# shinobi_solar.net
KiCad netlist of a schematic drawn in EAGLE
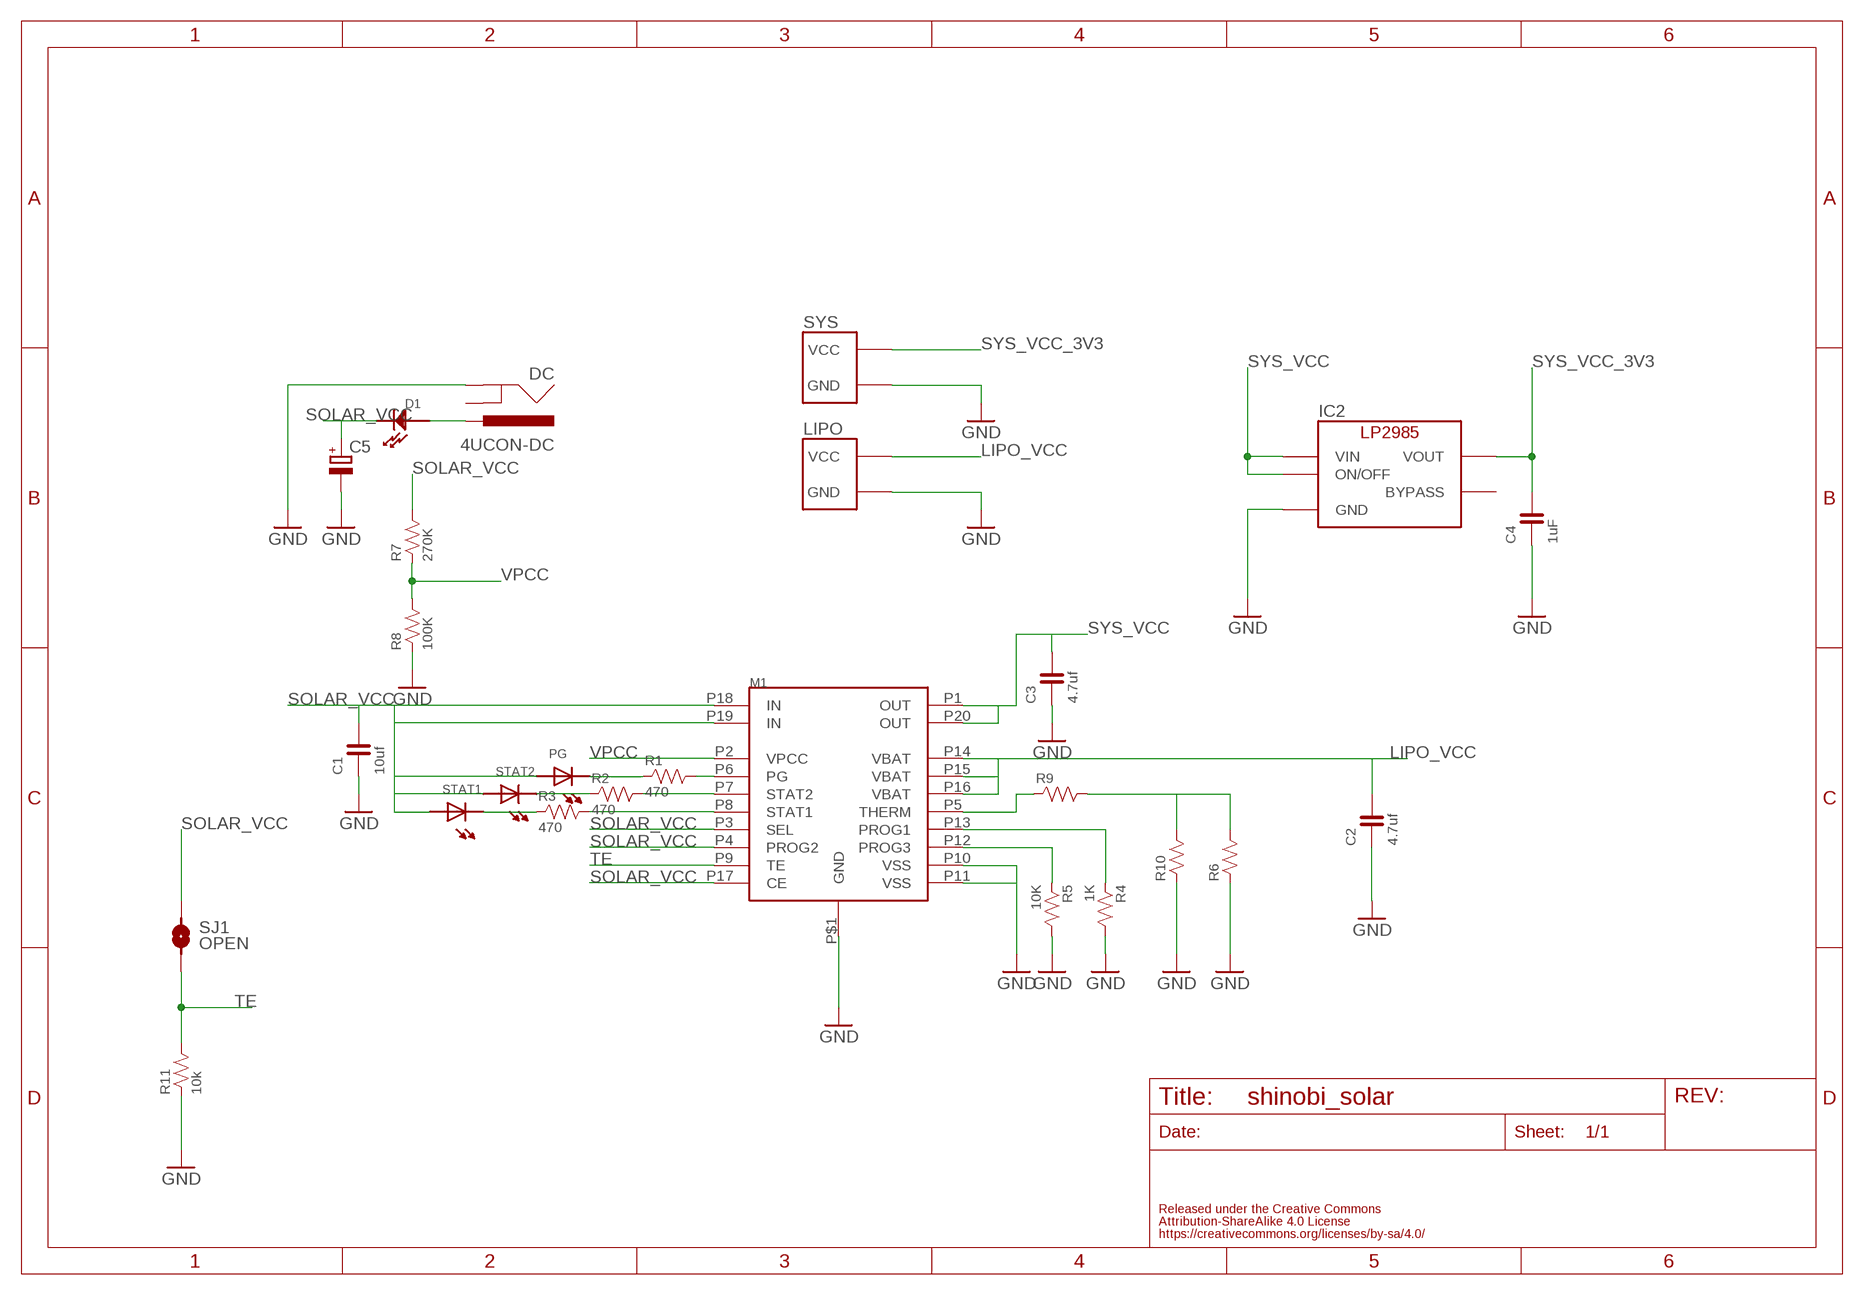
[diagram p0: schematic, sheet 1]

(export (version "E")
  (design (tool "Eeschema 10.0.6"))
  (components
    (comp (ref "C1")
      (value "10uf")
      (footprint "eagle-import:0603")
      (libsource (lib "eagle-import") (part "CAPACITOR-0603"))
    )
    (comp (ref "C2")
      (value "4.7uf")
      (footprint "eagle-import:0603")
      (libsource (lib "eagle-import") (part "CAPACITOR-0603"))
    )
    (comp (ref "C3")
      (value "4.7uf")
      (footprint "eagle-import:0603")
      (libsource (lib "eagle-import") (part "CAPACITOR-0603"))
    )
    (comp (ref "C4")
      (value "1uF")
      (footprint "eagle-import:0603")
      (libsource (lib "eagle-import") (part "CAPACITOR-0603"))
    )
    (comp (ref "C5")
      (value "CPOL-EUE5-13")
      (footprint "eagle-import:E5-13")
      (libsource (lib "eagle-import") (part "CPOL-EUE5-13"))
    )
    (comp (ref "D1")
      (value "DIODEDO-214AC")
      (footprint "eagle-import:DO-214AC")
      (libsource (lib "eagle-import") (part "DIODEDO-214AC"))
    )
    (comp (ref "DC")
      (value "4UCON-DC")
      (footprint "eagle-import:4UCON-DC")
      (libsource (lib "eagle-import") (part "4UCON-DC"))
    )
    (comp (ref "IC2")
      (value "LP2985-33DBV")
      (footprint "eagle-import:SOT-23-5")
      (libsource (lib "eagle-import") (part "LP2985-33DBV"))
    )
    (comp (ref "LIPO")
      (value "FABO_BRICK_2PIN_SIDE")
      (footprint "eagle-import:FABO_BRICK_2PIN_S02B−PASK-2_SILK")
      (libsource (lib "eagle-import") (part "FABO_BRICK_2PIN_SIDE"))
    )
    (comp (ref "M1")
      (value "MCP73871")
      (footprint "eagle-import:QFN")
      (libsource (lib "eagle-import") (part "MCP73871"))
    )
    (comp (ref "PG")
      (value "LED-0603")
      (footprint "eagle-import:0603")
      (libsource (lib "eagle-import") (part "LED-0603"))
    )
    (comp (ref "R1")
      (value "470")
      (footprint "eagle-import:0603")
      (libsource (lib "eagle-import") (part "RESISTOR-0603"))
    )
    (comp (ref "R2")
      (value "470")
      (footprint "eagle-import:0603")
      (libsource (lib "eagle-import") (part "RESISTOR-0603"))
    )
    (comp (ref "R3")
      (value "470")
      (footprint "eagle-import:0603")
      (libsource (lib "eagle-import") (part "RESISTOR-0603"))
    )
    (comp (ref "R4")
      (value "1K")
      (footprint "eagle-import:0603")
      (libsource (lib "eagle-import") (part "RESISTOR-0603"))
    )
    (comp (ref "R5")
      (value "10K")
      (footprint "eagle-import:0603")
      (libsource (lib "eagle-import") (part "RESISTOR-0603"))
    )
    (comp (ref "R6")
      (value "RESISTOR-0603")
      (footprint "eagle-import:0603")
      (libsource (lib "eagle-import") (part "RESISTOR-0603"))
    )
    (comp (ref "R7")
      (value "270K")
      (footprint "eagle-import:0603")
      (libsource (lib "eagle-import") (part "RESISTOR-0603"))
    )
    (comp (ref "R8")
      (value "100K")
      (footprint "eagle-import:0603")
      (libsource (lib "eagle-import") (part "RESISTOR-0603"))
    )
    (comp (ref "R9")
      (value "RESISTOR-0603")
      (footprint "eagle-import:0603")
      (libsource (lib "eagle-import") (part "RESISTOR-0603"))
    )
    (comp (ref "R10")
      (value "RESISTOR-AXL-REGULAR")
      (footprint "eagle-import:AXL-REGULAR")
      (libsource (lib "eagle-import") (part "RESISTOR-AXL-REGULAR"))
    )
    (comp (ref "R11")
      (value "10k")
      (footprint "eagle-import:0603")
      (libsource (lib "eagle-import") (part "RESISTOR-0603"))
    )
    (comp (ref "SJ1")
      (value "OPEN")
      (footprint "eagle-import:SMD-JUMPER-2")
      (libsource (lib "eagle-import") (part "SMD-JUMPER-2"))
    )
    (comp (ref "STAT1")
      (value "LED-0603")
      (footprint "eagle-import:0603")
      (libsource (lib "eagle-import") (part "LED-0603"))
    )
    (comp (ref "STAT2")
      (value "LED-0603")
      (footprint "eagle-import:0603")
      (libsource (lib "eagle-import") (part "LED-0603"))
    )
    (comp (ref "SYS")
      (value "FABO_BRICK_2PIN_SIDE")
      (footprint "eagle-import:FABO_BRICK_2PIN_S02B−PASK-2_SILK")
      (libsource (lib "eagle-import") (part "FABO_BRICK_2PIN_SIDE"))
    )
  )
  (nets
    (net (code "1") (name "/LIPO_VCC") (class "Default")
      (node (ref "C2") (pin "2") (pinfunction "2_2") (pintype "passive"))
      (node (ref "LIPO") (pin "VCC") (pinfunction "VCC_VCC") (pintype "bidirectional"))
      (node (ref "M1") (pin "P14") (pinfunction "VBAT_P14") (pintype "bidirectional"))
      (node (ref "M1") (pin "P15") (pinfunction "VBAT_P15") (pintype "bidirectional"))
      (node (ref "M1") (pin "P16") (pinfunction "VBAT_P16") (pintype "bidirectional"))
    )
    (net (code "2") (name "/SOLAR_VCC") (class "Default")
      (node (ref "C1") (pin "2") (pinfunction "2_2") (pintype "passive"))
      (node (ref "C5") (pin "+") (pinfunction "+_+") (pintype "passive"))
      (node (ref "D1") (pin "ANODE") (pinfunction "ANODE_ANODE") (pintype "bidirectional"))
      (node (ref "M1") (pin "P17") (pinfunction "CE_P17") (pintype "bidirectional"))
      (node (ref "M1") (pin "P18") (pinfunction "IN_P18") (pintype "bidirectional"))
      (node (ref "M1") (pin "P19") (pinfunction "IN_P19") (pintype "bidirectional"))
      (node (ref "M1") (pin "P3") (pinfunction "SEL_P3") (pintype "bidirectional"))
      (node (ref "M1") (pin "P4") (pinfunction "PROG2_P4") (pintype "bidirectional"))
      (node (ref "PG") (pin "ANODE") (pinfunction "ANODE_ANODE") (pintype "passive"))
      (node (ref "R7") (pin "2") (pinfunction "2_2") (pintype "bidirectional"))
      (node (ref "SJ1") (pin "1") (pinfunction "1_1") (pintype "passive"))
      (node (ref "STAT1") (pin "ANODE") (pinfunction "ANODE_ANODE") (pintype "passive"))
      (node (ref "STAT2") (pin "ANODE") (pinfunction "ANODE_ANODE") (pintype "passive"))
    )
    (net (code "3") (name "/SYS_VCC") (class "Default")
      (node (ref "C3") (pin "2") (pinfunction "2_2") (pintype "passive"))
      (node (ref "IC2") (pin "1") (pinfunction "VIN_1") (pintype "input"))
      (node (ref "IC2") (pin "3") (pinfunction "ON/OFF_3") (pintype "input"))
      (node (ref "M1") (pin "P1") (pinfunction "OUT_P1") (pintype "bidirectional"))
      (node (ref "M1") (pin "P20") (pinfunction "OUT_P20") (pintype "bidirectional"))
    )
    (net (code "4") (name "/SYS_VCC_3V3") (class "Default")
      (node (ref "C4") (pin "2") (pinfunction "2_2") (pintype "passive"))
      (node (ref "IC2") (pin "5") (pinfunction "VOUT_5") (pintype "output"))
      (node (ref "SYS") (pin "VCC") (pinfunction "VCC_VCC") (pintype "bidirectional"))
    )
    (net (code "5") (name "/TE") (class "Default")
      (node (ref "M1") (pin "P9") (pinfunction "TE_P9") (pintype "bidirectional"))
      (node (ref "R11") (pin "2") (pinfunction "2_2") (pintype "bidirectional"))
      (node (ref "SJ1") (pin "2") (pinfunction "2_2") (pintype "passive"))
    )
    (net (code "6") (name "/VPCC") (class "Default")
      (node (ref "M1") (pin "P2") (pinfunction "VPCC_P2") (pintype "bidirectional"))
      (node (ref "R7") (pin "1") (pinfunction "1_1") (pintype "bidirectional"))
      (node (ref "R8") (pin "2") (pinfunction "2_2") (pintype "bidirectional"))
    )
    (net (code "7") (name "GND") (class "Default")
      (node (ref "C1") (pin "1") (pinfunction "1_1") (pintype "passive"))
      (node (ref "C2") (pin "1") (pinfunction "1_1") (pintype "passive"))
      (node (ref "C3") (pin "1") (pinfunction "1_1") (pintype "passive"))
      (node (ref "C4") (pin "1") (pinfunction "1_1") (pintype "passive"))
      (node (ref "C5") (pin "-") (pinfunction "-_-") (pintype "passive"))
      (node (ref "DC") (pin "GND1") (pinfunction "GND_GND1") (pintype "bidirectional"))
      (node (ref "IC2") (pin "2") (pinfunction "GND_2") (pintype "power_in"))
      (node (ref "LIPO") (pin "GND") (pinfunction "GND_GND") (pintype "bidirectional"))
      (node (ref "M1") (pin "P$1") (pinfunction "GND_P$1") (pintype "bidirectional"))
      (node (ref "M1") (pin "P10") (pinfunction "VSS_P10") (pintype "bidirectional"))
      (node (ref "M1") (pin "P11") (pinfunction "VSS_P11") (pintype "bidirectional"))
      (node (ref "R10") (pin "1") (pinfunction "1_1") (pintype "bidirectional"))
      (node (ref "R11") (pin "1") (pinfunction "1_1") (pintype "bidirectional"))
      (node (ref "R4") (pin "2") (pinfunction "2_2") (pintype "bidirectional"))
      (node (ref "R5") (pin "2") (pinfunction "2_2") (pintype "bidirectional"))
      (node (ref "R6") (pin "1") (pinfunction "1_1") (pintype "bidirectional"))
      (node (ref "R8") (pin "1") (pinfunction "1_1") (pintype "bidirectional"))
      (node (ref "SYS") (pin "GND") (pinfunction "GND_GND") (pintype "bidirectional"))
    )
    (net (code "8") (name "Net-(DC-PWR)") (class "Default")
      (node (ref "D1") (pin "CATHODE") (pinfunction "CATHODE_CATHODE") (pintype "bidirectional"))
      (node (ref "DC") (pin "VCC") (pinfunction "PWR_VCC") (pintype "bidirectional"))
    )
    (net (code "9") (name "Net-(M1-PG)") (class "Default")
      (node (ref "M1") (pin "P6") (pinfunction "PG_P6") (pintype "bidirectional"))
      (node (ref "R1") (pin "2") (pinfunction "2_2") (pintype "bidirectional"))
    )
    (net (code "10") (name "Net-(M1-PROG1)") (class "Default")
      (node (ref "M1") (pin "P13") (pinfunction "PROG1_P13") (pintype "bidirectional"))
      (node (ref "R4") (pin "1") (pinfunction "1_1") (pintype "bidirectional"))
    )
    (net (code "11") (name "Net-(M1-PROG3)") (class "Default")
      (node (ref "M1") (pin "P12") (pinfunction "PROG3_P12") (pintype "bidirectional"))
      (node (ref "R5") (pin "1") (pinfunction "1_1") (pintype "bidirectional"))
    )
    (net (code "12") (name "Net-(M1-STAT1)") (class "Default")
      (node (ref "M1") (pin "P8") (pinfunction "STAT1_P8") (pintype "bidirectional"))
      (node (ref "R3") (pin "2") (pinfunction "2_2") (pintype "bidirectional"))
    )
    (net (code "13") (name "Net-(M1-STAT2)") (class "Default")
      (node (ref "M1") (pin "P7") (pinfunction "STAT2_P7") (pintype "bidirectional"))
      (node (ref "R2") (pin "2") (pinfunction "2_2") (pintype "bidirectional"))
    )
    (net (code "14") (name "Net-(M1-THERM)") (class "Default")
      (node (ref "M1") (pin "P5") (pinfunction "THERM_P5") (pintype "bidirectional"))
      (node (ref "R9") (pin "1") (pinfunction "1_1") (pintype "bidirectional"))
    )
    (net (code "15") (name "Net-(PG-PadCATHODE)") (class "Default")
      (node (ref "PG") (pin "CATHODE") (pinfunction "CATHODE_CATHODE") (pintype "passive"))
      (node (ref "R1") (pin "1") (pinfunction "1_1") (pintype "bidirectional"))
    )
    (net (code "16") (name "Net-(R2-Pad1)") (class "Default")
      (node (ref "R2") (pin "1") (pinfunction "1_1") (pintype "bidirectional"))
      (node (ref "STAT2") (pin "CATHODE") (pinfunction "CATHODE_CATHODE") (pintype "passive"))
    )
    (net (code "17") (name "Net-(R3-Pad1)") (class "Default")
      (node (ref "R3") (pin "1") (pinfunction "1_1") (pintype "bidirectional"))
      (node (ref "STAT1") (pin "CATHODE") (pinfunction "CATHODE_CATHODE") (pintype "passive"))
    )
    (net (code "18") (name "Net-(R10-Pad2)") (class "Default")
      (node (ref "R10") (pin "2") (pinfunction "2_2") (pintype "bidirectional"))
      (node (ref "R6") (pin "2") (pinfunction "2_2") (pintype "bidirectional"))
      (node (ref "R9") (pin "2") (pinfunction "2_2") (pintype "bidirectional"))
    )
    (net (code "19") (name "unconnected-(DC-GNDBREAK-PadGND2)") (class "Default")
      (node (ref "DC") (pin "GND2") (pinfunction "GNDBREAK_GND2") (pintype "bidirectional"))
    )
    (net (code "20") (name "unconnected-(IC2-BYPASS-Pad4)") (class "Default")
      (node (ref "IC2") (pin "4") (pinfunction "BYPASS_4") (pintype "bidirectional"))
    )
  )
)
